# Current_Sensor.net
KiCad netlist of a schematic drawn in Altium Designer
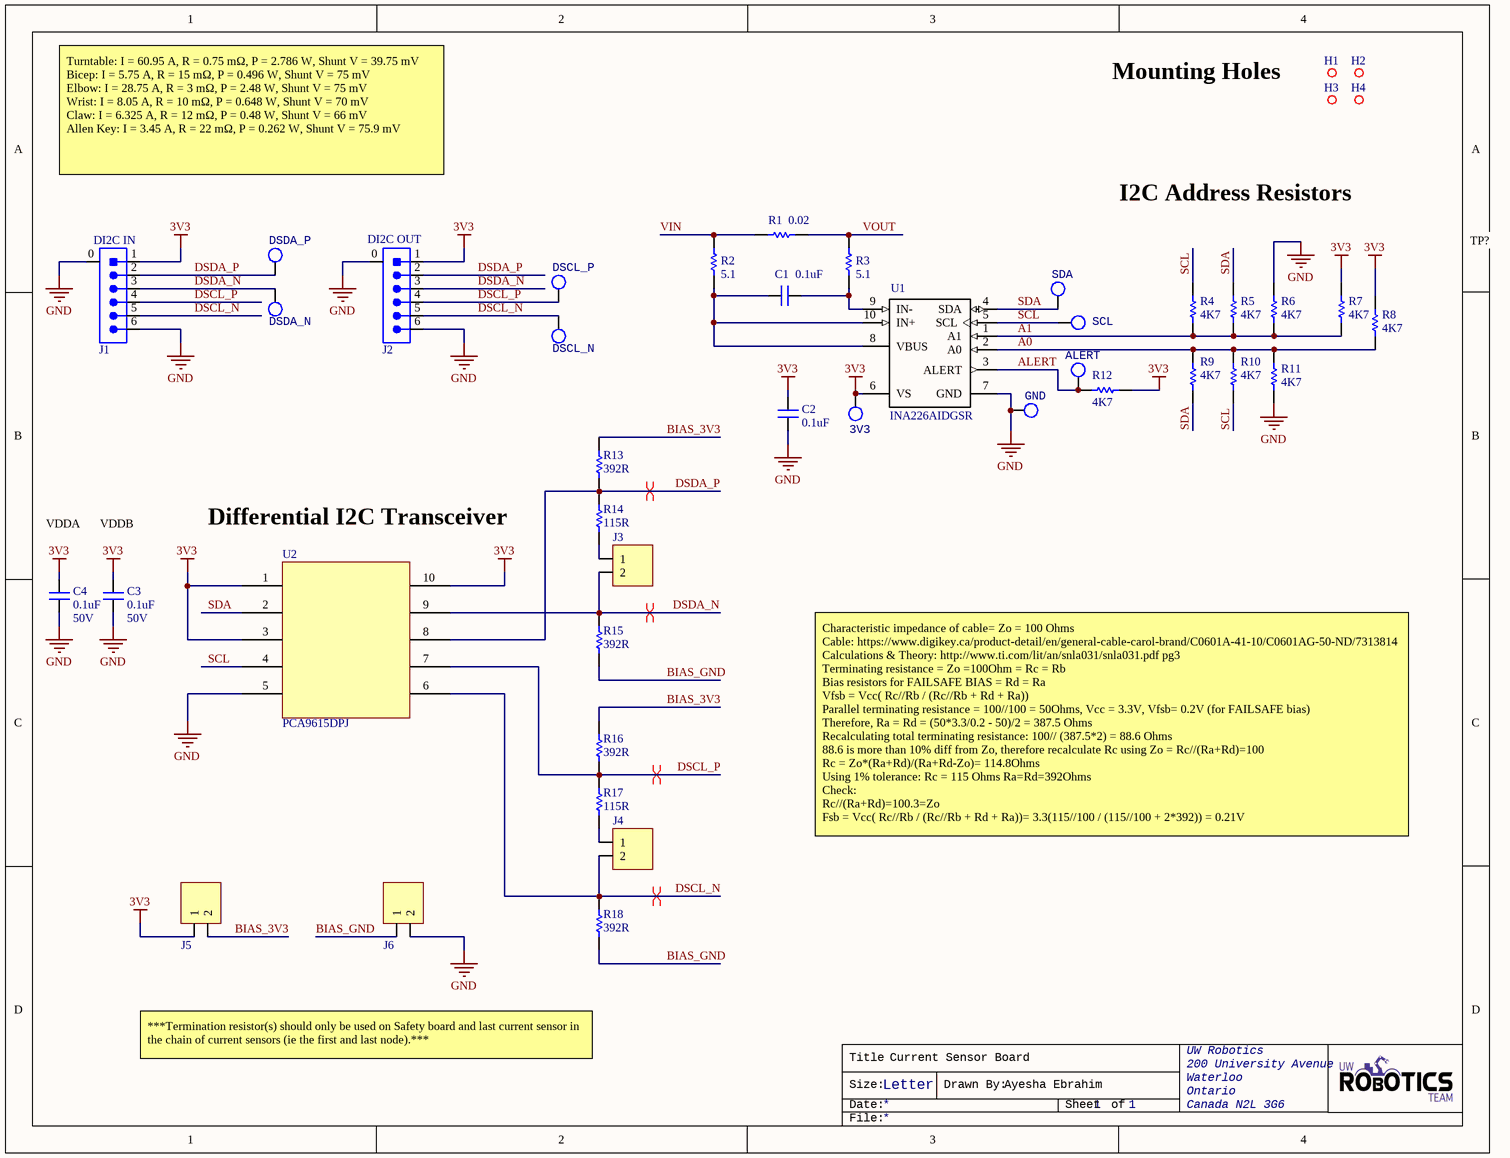
[diagram p0: Current Sensor.SchDoc]

(export (version "E")
  (design (tool "Eeschema 10.0.6"))
  (components
    (comp (ref "C1")
      (value "0.1uF")
      (footprint "CAPC2012X140N")
      (description "CAP CER 0.1UF 50V X7R 0805")
      (fields (field (name "TOLERANCE") "10%") (field (name "Comment") "CAP_0.1uF_50V_0805"))
      (libsource (lib "UWRT_Schematic_Library_2020") (part "CAP_0.1uF_50V_0805"))
    )
    (comp (ref "C2")
      (value "0.1uF")
      (footprint "CAPC2012X140N")
      (description "CAP CER 0.1UF 50V X7R 0805")
      (fields (field (name "TOLERANCE") "10%") (field (name "Comment") "CAP_0.1uF_50V_0805"))
      (libsource (lib "UWRT_Schematic_Library_2020") (part "CAP_0.1uF_50V_0805"))
    )
    (comp (ref "C3")
      (value "0.1uF")
      (footprint "CAPC2012X140N")
      (description "CAP CER 0.1UF 50V X7R 0805")
      (fields
        (field (name "TOLERANCE") "10%")
        (field (name "VOLTAGE RATING") "50V")
        (field (name "Comment") "CAP_0.1uF_50V_0805")
      )
      (libsource (lib "UWRT_Schematic_Library_2020") (part "CAP_0.1uF_50V_0805"))
    )
    (comp (ref "C4")
      (value "0.1uF")
      (footprint "CAPC2012X140N")
      (description "CAP CER 0.1UF 50V X7R 0805")
      (fields
        (field (name "TOLERANCE") "10%")
        (field (name "VOLTAGE RATING") "50V")
        (field (name "Comment") "CAP_0.1uF_50V_0805")
      )
      (libsource (lib "UWRT_Schematic_Library_2020") (part "CAP_0.1uF_50V_0805"))
    )
    (comp (ref "H1")
      (value "MOUNTING_HOLES")
      (footprint "MOUNTING_HOLE")
      (description "6cm x 6cm")
      (libsource (lib "UWRT_Schematic_Library_2020") (part "MOUNTING_HOLES"))
    )
    (comp (ref "H2")
      (value "MOUNTING_HOLES")
      (footprint "MOUNTING_HOLE")
      (description "6cm x 6cm")
      (libsource (lib "UWRT_Schematic_Library_2020") (part "MOUNTING_HOLES"))
    )
    (comp (ref "H3")
      (value "MOUNTING_HOLES")
      (footprint "MOUNTING_HOLE")
      (description "6cm x 6cm")
      (libsource (lib "UWRT_Schematic_Library_2020") (part "MOUNTING_HOLES"))
    )
    (comp (ref "H4")
      (value "MOUNTING_HOLES")
      (footprint "MOUNTING_HOLE")
      (description "6cm x 6cm")
      (libsource (lib "UWRT_Schematic_Library_2020") (part "MOUNTING_HOLES"))
    )
    (comp (ref "J1")
      (value "DI2C IN")
      (footprint "MOLEX-5024940670")
      (description "CONN HEADER SMD RIGHT ANGLE 2MM PITCH")
      (libsource (lib "UWRT_Schematic_Library_2020") (part "CON_6M_SM_RA"))
    )
    (comp (ref "J2")
      (value "DI2C OUT")
      (footprint "MOLEX-5024940670")
      (description "CONN HEADER SMD RIGHT ANGLE 2MM PITCH")
      (libsource (lib "UWRT_Schematic_Library_2020") (part "CON_6M_SM_RA"))
    )
    (comp (ref "J3")
      (value "JUMPER_2")
      (footprint "HDR1X2")
      (description "HEADER 2X1")
      (libsource (lib "UWRT_Schematic_Library_2020") (part "JUMPER_2"))
    )
    (comp (ref "J4")
      (value "JUMPER_2")
      (footprint "HDR1X2")
      (description "HEADER 2X1")
      (libsource (lib "UWRT_Schematic_Library_2020") (part "JUMPER_2"))
    )
    (comp (ref "J5")
      (value "JUMPER_2")
      (footprint "HDR1X2")
      (description "HEADER 2X1")
      (libsource (lib "") (part "JUMPER_2_1"))
    )
    (comp (ref "J6")
      (value "JUMPER_2")
      (footprint "HDR1X2")
      (description "HEADER 2X1")
      (libsource (lib "") (part "JUMPER_2_1"))
    )
    (comp (ref "R1")
      (value "0.02")
      (footprint "RESC6532X75N")
      (description "RES 0.02 OHM 1% 3W 2512")
      (fields (field (name "Comment") "RES_20m_2512"))
      (libsource (lib "UWRT_Schematic_Library_2020") (part "RES_20m_2512"))
    )
    (comp (ref "R2")
      (value "5.1")
      (footprint "RESC2013X70X40LL20T20")
      (description "RES SMD 5.1 OHM 5% 1/8W 0805")
      (fields (field (name "PART NUMBER") "ERJ-6GEYJ5R1V") (field (name "MANUFACTURER") "Panasonic"))
      (libsource (lib "UWRT_Schematic_Library_2020") (part "RES_5.1_0805"))
    )
    (comp (ref "R3")
      (value "5.1")
      (footprint "RESC2013X70X40LL20T20")
      (description "RES SMD 5.1 OHM 5% 1/8W 0805")
      (fields (field (name "PART NUMBER") "ERJ-6GEYJ5R1V") (field (name "MANUFACTURER") "Panasonic"))
      (libsource (lib "UWRT_Schematic_Library_2020") (part "RES_5.1_0805"))
    )
    (comp (ref "R4")
      (value "4K7")
      (footprint "RESC2012X60N")
      (description "RES SMD 4.7K OHM 5% 1/8W 0805")
      (fields (field (name "TOLERANCE") "5%") (field (name "Comment") "RES_4K7_0805"))
      (libsource (lib "UWRT_Schematic_Library_2020") (part "RES_4K7_0805"))
    )
    (comp (ref "R5")
      (value "4K7")
      (footprint "RESC2012X60N")
      (description "RES SMD 4.7K OHM 5% 1/8W 0805")
      (fields (field (name "TOLERANCE") "5%") (field (name "Comment") "RES_4K7_0805"))
      (libsource (lib "UWRT_Schematic_Library_2020") (part "RES_4K7_0805"))
    )
    (comp (ref "R6")
      (value "4K7")
      (footprint "RESC2012X60N")
      (description "RES SMD 4.7K OHM 5% 1/8W 0805")
      (fields (field (name "TOLERANCE") "5%") (field (name "Comment") "RES_4K7_0805"))
      (libsource (lib "UWRT_Schematic_Library_2020") (part "RES_4K7_0805"))
    )
    (comp (ref "R7")
      (value "4K7")
      (footprint "RESC2012X60N")
      (description "RES SMD 4.7K OHM 5% 1/8W 0805")
      (fields (field (name "TOLERANCE") "5%") (field (name "Comment") "RES_4K7_0805"))
      (libsource (lib "UWRT_Schematic_Library_2020") (part "RES_4K7_0805"))
    )
    (comp (ref "R8")
      (value "4K7")
      (footprint "RESC2012X60N")
      (description "RES SMD 4.7K OHM 5% 1/8W 0805")
      (fields (field (name "TOLERANCE") "5%") (field (name "Comment") "RES_4K7_0805"))
      (libsource (lib "UWRT_Schematic_Library_2020") (part "RES_4K7_0805"))
    )
    (comp (ref "R9")
      (value "4K7")
      (footprint "RESC2012X60N")
      (description "RES SMD 4.7K OHM 5% 1/8W 0805")
      (fields (field (name "TOLERANCE") "5%") (field (name "Comment") "RES_4K7_0805"))
      (libsource (lib "UWRT_Schematic_Library_2020") (part "RES_4K7_0805"))
    )
    (comp (ref "R10")
      (value "4K7")
      (footprint "RESC2012X60N")
      (description "RES SMD 4.7K OHM 5% 1/8W 0805")
      (fields (field (name "TOLERANCE") "5%") (field (name "Comment") "RES_4K7_0805"))
      (libsource (lib "UWRT_Schematic_Library_2020") (part "RES_4K7_0805"))
    )
    (comp (ref "R11")
      (value "4K7")
      (footprint "RESC2012X60N")
      (description "RES SMD 4.7K OHM 5% 1/8W 0805")
      (fields (field (name "TOLERANCE") "5%") (field (name "Comment") "RES_4K7_0805"))
      (libsource (lib "UWRT_Schematic_Library_2020") (part "RES_4K7_0805"))
    )
    (comp (ref "R12")
      (value "4K7")
      (footprint "RESC2012X60N")
      (description "RES SMD 4.7K OHM 5% 1/8W 0805")
      (fields (field (name "TOLERANCE") "5%") (field (name "Comment") "RES_4K7_0805"))
      (libsource (lib "UWRT_Schematic_Library_2020") (part "RES_4K7_0805"))
    )
    (comp (ref "R13")
      (value "RES_392R_0805")
      (footprint "RESC2012X60N")
      (description "RES SMD 392 OHM 1% 1/8W 0805")
      (fields
        (field (name "MANUFACTURER PART NUMBER") "RC0805FR-07392RL")
        (field (name "TOLERANCE") "1%")
        (field (name "RESISTANCE") "392R")
      )
      (libsource (lib "UWRT_Schematic_Library_2020") (part "RES_392R_0805"))
    )
    (comp (ref "R14")
      (value "RES_115R_0805")
      (footprint "RESC2012X60N")
      (description "RES SMD 115 OHM 1% 1/8W 0805")
      (fields
        (field (name "MANUFACTURER PART NUMBER") "RC0805FR-07115RL")
        (field (name "TOLERANCE") "1%")
        (field (name "RESISTANCE") "115R")
      )
      (libsource (lib "UWRT_Schematic_Library_2020") (part "RES_115R_0805"))
    )
    (comp (ref "R15")
      (value "RES_392R_0805")
      (footprint "RESC2012X60N")
      (description "RES SMD 392 OHM 1% 1/8W 0805")
      (fields
        (field (name "MANUFACTURER PART NUMBER") "RC0805FR-07392RL")
        (field (name "TOLERANCE") "1%")
        (field (name "RESISTANCE") "392R")
      )
      (libsource (lib "UWRT_Schematic_Library_2020") (part "RES_392R_0805"))
    )
    (comp (ref "R16")
      (value "RES_392R_0805")
      (footprint "RESC2012X60N")
      (description "RES SMD 392 OHM 1% 1/8W 0805")
      (fields
        (field (name "MANUFACTURER PART NUMBER") "RC0805FR-07392RL")
        (field (name "TOLERANCE") "1%")
        (field (name "RESISTANCE") "392R")
      )
      (libsource (lib "UWRT_Schematic_Library_2020") (part "RES_392R_0805"))
    )
    (comp (ref "R17")
      (value "RES_115R_0805")
      (footprint "RESC2012X60N")
      (description "RES SMD 115 OHM 1% 1/8W 0805")
      (fields
        (field (name "MANUFACTURER PART NUMBER") "RC0805FR-07115RL")
        (field (name "TOLERANCE") "1%")
        (field (name "RESISTANCE") "115R")
      )
      (libsource (lib "UWRT_Schematic_Library_2020") (part "RES_115R_0805"))
    )
    (comp (ref "R18")
      (value "RES_392R_0805")
      (footprint "RESC2012X60N")
      (description "RES SMD 392 OHM 1% 1/8W 0805")
      (fields
        (field (name "MANUFACTURER PART NUMBER") "RC0805FR-07392RL")
        (field (name "TOLERANCE") "1%")
        (field (name "RESISTANCE") "392R")
      )
      (libsource (lib "UWRT_Schematic_Library_2020") (part "RES_392R_0805"))
    )
    (comp (ref "TP1")
      (value "DSDA_P")
      (footprint "TESTPOINT_LOOP")
      (description "Loop testpoint through-hole pad")
      (libsource (lib "UWRT_Schematic_Library_2020") (part "TESTPOINT_LOOP"))
    )
    (comp (ref "TP2")
      (value "DSCL_P")
      (footprint "TESTPOINT_LOOP")
      (description "Loop testpoint through-hole pad")
      (libsource (lib "UWRT_Schematic_Library_2020") (part "TESTPOINT_LOOP"))
    )
    (comp (ref "TP3")
      (value "SDA")
      (footprint "TESTPOINT_LOOP")
      (description "Loop testpoint through-hole pad")
      (fields (field (name "MANUFACTURER") "Keystone Electronics"))
      (libsource (lib "UWRT_Schematic_Library_2020") (part "TESTPOINT_LOOP"))
    )
    (comp (ref "TP4")
      (value "DSDA_N")
      (footprint "TESTPOINT_LOOP")
      (description "Loop testpoint through-hole pad")
      (libsource (lib "UWRT_Schematic_Library_2020") (part "TESTPOINT_LOOP"))
    )
    (comp (ref "TP5")
      (value "SCL")
      (footprint "TESTPOINT_LOOP")
      (description "Loop testpoint through-hole pad")
      (fields (field (name "MANUFACTURER") "Keystone Electronics"))
      (libsource (lib "UWRT_Schematic_Library_2020") (part "TESTPOINT_LOOP"))
    )
    (comp (ref "TP6")
      (value "DSCL_N")
      (footprint "TESTPOINT_LOOP")
      (description "Loop testpoint through-hole pad")
      (libsource (lib "UWRT_Schematic_Library_2020") (part "TESTPOINT_LOOP"))
    )
    (comp (ref "TP7")
      (value "ALERT")
      (footprint "TESTPOINT_LOOP")
      (description "Loop testpoint through-hole pad")
      (fields (field (name "MANUFACTURER") "Keystone Electronics"))
      (libsource (lib "UWRT_Schematic_Library_2020") (part "TESTPOINT_LOOP"))
    )
    (comp (ref "TP8")
      (value "GND")
      (footprint "TESTPOINT_LOOP")
      (description "Loop testpoint through-hole pad")
      (fields (field (name "MANUFACTURER") "Keystone Electronics"))
      (libsource (lib "UWRT_Schematic_Library_2020") (part "TESTPOINT_LOOP"))
    )
    (comp (ref "TP9")
      (value "3V3")
      (footprint "TESTPOINT_LOOP")
      (description "Loop testpoint through-hole pad")
      (fields (field (name "MANUFACTURER") "Keystone Electronics"))
      (libsource (lib "UWRT_Schematic_Library_2020") (part "TESTPOINT_LOOP"))
    )
    (comp (ref "U1")
      (value "INA226AIDGSR")
      (footprint "INA226AIDGSR")
      (description "IC MONITOR PWR/CURR BIDIR 10MSOP")
      (fields (field (name "MF") "Texas Instruments"))
      (libsource (lib "UWRT_Schematic_Library_2020") (part "INA226AIDGSR"))
    )
    (comp (ref "U2")
      (value "DIFF_I2C_BUFFER")
      (footprint "PCA9615DPJ")
      (description "IC DIFF I2C BUFFER 2CH 10TSSOP")
      (fields (field (name "MANUFACTURER PART NUMBER 1") "PCA9615DPJ"))
      (libsource (lib "UWRT_Schematic_Library_2020") (part "DIFF_I2C_BUFFER"))
    )
  )
  (nets
    (net (code "1") (name "/A0") (class "Default")
      (node (ref "R10") (pin "1") (pinfunction "1_1") (pintype "passive"))
      (node (ref "R11") (pin "1") (pinfunction "1_1") (pintype "passive"))
      (node (ref "R8") (pin "1") (pinfunction "1_1") (pintype "passive"))
      (node (ref "R9") (pin "1") (pinfunction "1_1") (pintype "passive"))
      (node (ref "U1") (pin "2") (pinfunction "A0_2") (pintype "input"))
    )
    (net (code "2") (name "/A1") (class "Default")
      (node (ref "R4") (pin "1") (pinfunction "1_1") (pintype "passive"))
      (node (ref "R5") (pin "1") (pinfunction "1_1") (pintype "passive"))
      (node (ref "R6") (pin "1") (pinfunction "1_1") (pintype "passive"))
      (node (ref "R7") (pin "1") (pinfunction "1_1") (pintype "passive"))
      (node (ref "U1") (pin "1") (pinfunction "A1_1") (pintype "input"))
    )
    (net (code "3") (name "/ALERT") (class "Default")
      (node (ref "R12") (pin "1") (pinfunction "1_1") (pintype "passive"))
      (node (ref "TP7") (pin "1") (pintype "passive"))
      (node (ref "U1") (pin "3") (pinfunction "ALERT_3") (pintype "output"))
    )
    (net (code "4") (name "/BIAS_3V3") (class "Default")
      (node (ref "J5") (pin "2") (pinfunction "2_2") (pintype "passive"))
      (node (ref "R13") (pin "2") (pinfunction "2_2") (pintype "passive"))
      (node (ref "R16") (pin "2") (pinfunction "2_2") (pintype "passive"))
    )
    (net (code "5") (name "/BIAS_GND") (class "Default")
      (node (ref "J6") (pin "1") (pinfunction "1_1") (pintype "passive"))
      (node (ref "R15") (pin "1") (pinfunction "1_1") (pintype "passive"))
      (node (ref "R18") (pin "1") (pinfunction "1_1") (pintype "passive"))
    )
    (net (code "6") (name "/DSCL_N") (class "Default")
      (node (ref "J1") (pin "5") (pinfunction "5_5") (pintype "passive"))
      (node (ref "J2") (pin "5") (pinfunction "5_5") (pintype "passive"))
      (node (ref "J4") (pin "2") (pinfunction "2_2") (pintype "passive"))
      (node (ref "R18") (pin "2") (pinfunction "2_2") (pintype "passive"))
      (node (ref "TP6") (pin "1") (pintype "passive"))
      (node (ref "U2") (pin "6") (pinfunction "DSCLM_6") (pintype "passive"))
    )
    (net (code "7") (name "/DSCL_P") (class "Default")
      (node (ref "J1") (pin "4") (pinfunction "4_4") (pintype "passive"))
      (node (ref "J2") (pin "4") (pinfunction "4_4") (pintype "passive"))
      (node (ref "R16") (pin "1") (pinfunction "1_1") (pintype "passive"))
      (node (ref "R17") (pin "2") (pinfunction "2_2") (pintype "passive"))
      (node (ref "TP2") (pin "1") (pintype "passive"))
      (node (ref "U2") (pin "7") (pinfunction "DSCLP_7") (pintype "passive"))
    )
    (net (code "8") (name "/DSDA_N") (class "Default")
      (node (ref "J1") (pin "3") (pinfunction "3_3") (pintype "passive"))
      (node (ref "J2") (pin "3") (pinfunction "3_3") (pintype "passive"))
      (node (ref "J3") (pin "2") (pinfunction "2_2") (pintype "passive"))
      (node (ref "R15") (pin "2") (pinfunction "2_2") (pintype "passive"))
      (node (ref "TP4") (pin "1") (pintype "passive"))
      (node (ref "U2") (pin "9") (pinfunction "DSDAM_9") (pintype "passive"))
    )
    (net (code "9") (name "/DSDA_P") (class "Default")
      (node (ref "J1") (pin "2") (pinfunction "2_2") (pintype "passive"))
      (node (ref "J2") (pin "2") (pinfunction "2_2") (pintype "passive"))
      (node (ref "R13") (pin "1") (pinfunction "1_1") (pintype "passive"))
      (node (ref "R14") (pin "2") (pinfunction "2_2") (pintype "passive"))
      (node (ref "TP1") (pin "1") (pintype "passive"))
      (node (ref "U2") (pin "8") (pinfunction "DSDAP_8") (pintype "passive"))
    )
    (net (code "10") (name "/SCL") (class "Default")
      (node (ref "R10") (pin "2") (pinfunction "2_2") (pintype "passive"))
      (node (ref "R4") (pin "2") (pinfunction "2_2") (pintype "passive"))
      (node (ref "TP5") (pin "1") (pintype "passive"))
      (node (ref "U1") (pin "5") (pinfunction "SCL_5") (pintype "input"))
      (node (ref "U2") (pin "4") (pinfunction "SCL_4") (pintype "passive"))
    )
    (net (code "11") (name "/SDA") (class "Default")
      (node (ref "R5") (pin "2") (pinfunction "2_2") (pintype "passive"))
      (node (ref "R9") (pin "2") (pinfunction "2_2") (pintype "passive"))
      (node (ref "TP3") (pin "1") (pintype "passive"))
      (node (ref "U1") (pin "4") (pinfunction "SDA_4") (pintype "bidirectional"))
      (node (ref "U2") (pin "2") (pinfunction "SDA_2") (pintype "passive"))
    )
    (net (code "12") (name "/VIN") (class "Default")
      (node (ref "R1") (pin "1") (pinfunction "1_1") (pintype "passive"))
      (node (ref "R2") (pin "2") (pinfunction "2_2") (pintype "passive"))
    )
    (net (code "13") (name "/VOUT") (class "Default")
      (node (ref "R1") (pin "2") (pinfunction "2_2") (pintype "passive"))
      (node (ref "R3") (pin "2") (pinfunction "2_2") (pintype "passive"))
    )
    (net (code "14") (name "3V3") (class "Default")
      (node (ref "C2") (pin "2") (pinfunction "2_2") (pintype "passive"))
      (node (ref "C3") (pin "2") (pinfunction "2_2") (pintype "passive"))
      (node (ref "C4") (pin "2") (pinfunction "2_2") (pintype "passive"))
      (node (ref "J1") (pin "1") (pinfunction "1_1") (pintype "passive"))
      (node (ref "J2") (pin "1") (pinfunction "1_1") (pintype "passive"))
      (node (ref "J5") (pin "1") (pinfunction "1_1") (pintype "passive"))
      (node (ref "R12") (pin "2") (pinfunction "2_2") (pintype "passive"))
      (node (ref "R7") (pin "2") (pinfunction "2_2") (pintype "passive"))
      (node (ref "R8") (pin "2") (pinfunction "2_2") (pintype "passive"))
      (node (ref "TP9") (pin "1") (pintype "passive"))
      (node (ref "U1") (pin "6") (pinfunction "VS_6") (pintype "power_in"))
      (node (ref "U2") (pin "1") (pinfunction "VDDA_1") (pintype "passive"))
      (node (ref "U2") (pin "10") (pinfunction "VDDB_10") (pintype "passive"))
      (node (ref "U2") (pin "3") (pinfunction "EN_3") (pintype "passive"))
    )
    (net (code "15") (name "GND") (class "Default")
      (node (ref "C2") (pin "1") (pinfunction "1_1") (pintype "passive"))
      (node (ref "C3") (pin "1") (pinfunction "1_1") (pintype "passive"))
      (node (ref "C4") (pin "1") (pinfunction "1_1") (pintype "passive"))
      (node (ref "J1") (pin "0") (pinfunction "0_0") (pintype "passive"))
      (node (ref "J1") (pin "6") (pinfunction "6_6") (pintype "passive"))
      (node (ref "J2") (pin "0") (pinfunction "0_0") (pintype "passive"))
      (node (ref "J2") (pin "6") (pinfunction "6_6") (pintype "passive"))
      (node (ref "J6") (pin "2") (pinfunction "2_2") (pintype "passive"))
      (node (ref "R11") (pin "2") (pinfunction "2_2") (pintype "passive"))
      (node (ref "R6") (pin "2") (pinfunction "2_2") (pintype "passive"))
      (node (ref "TP8") (pin "1") (pintype "passive"))
      (node (ref "U1") (pin "7") (pinfunction "GND_7") (pintype "power_in"))
      (node (ref "U2") (pin "5") (pinfunction "VSS_5") (pintype "passive"))
    )
    (net (code "16") (name "Net-(J3-Pad1)") (class "Default")
      (node (ref "J3") (pin "1") (pinfunction "1_1") (pintype "passive"))
      (node (ref "R14") (pin "1") (pinfunction "1_1") (pintype "passive"))
    )
    (net (code "17") (name "Net-(J4-Pad1)") (class "Default")
      (node (ref "J4") (pin "1") (pinfunction "1_1") (pintype "passive"))
      (node (ref "R17") (pin "1") (pinfunction "1_1") (pintype "passive"))
    )
    (net (code "18") (name "Net-(U1-IN+)") (class "Default")
      (node (ref "C1") (pin "1") (pinfunction "1_1") (pintype "passive"))
      (node (ref "R2") (pin "1") (pinfunction "1_1") (pintype "passive"))
      (node (ref "U1") (pin "10") (pinfunction "IN+_10") (pintype "input"))
      (node (ref "U1") (pin "8") (pinfunction "VBUS_8") (pintype "power_in"))
    )
    (net (code "19") (name "Net-(U1-IN-)") (class "Default")
      (node (ref "C1") (pin "2") (pinfunction "2_2") (pintype "passive"))
      (node (ref "R3") (pin "1") (pinfunction "1_1") (pintype "passive"))
      (node (ref "U1") (pin "9") (pinfunction "IN-_9") (pintype "input"))
    )
  )
)
